# hub.net
KiCad netlist of a schematic drawn in EAGLE
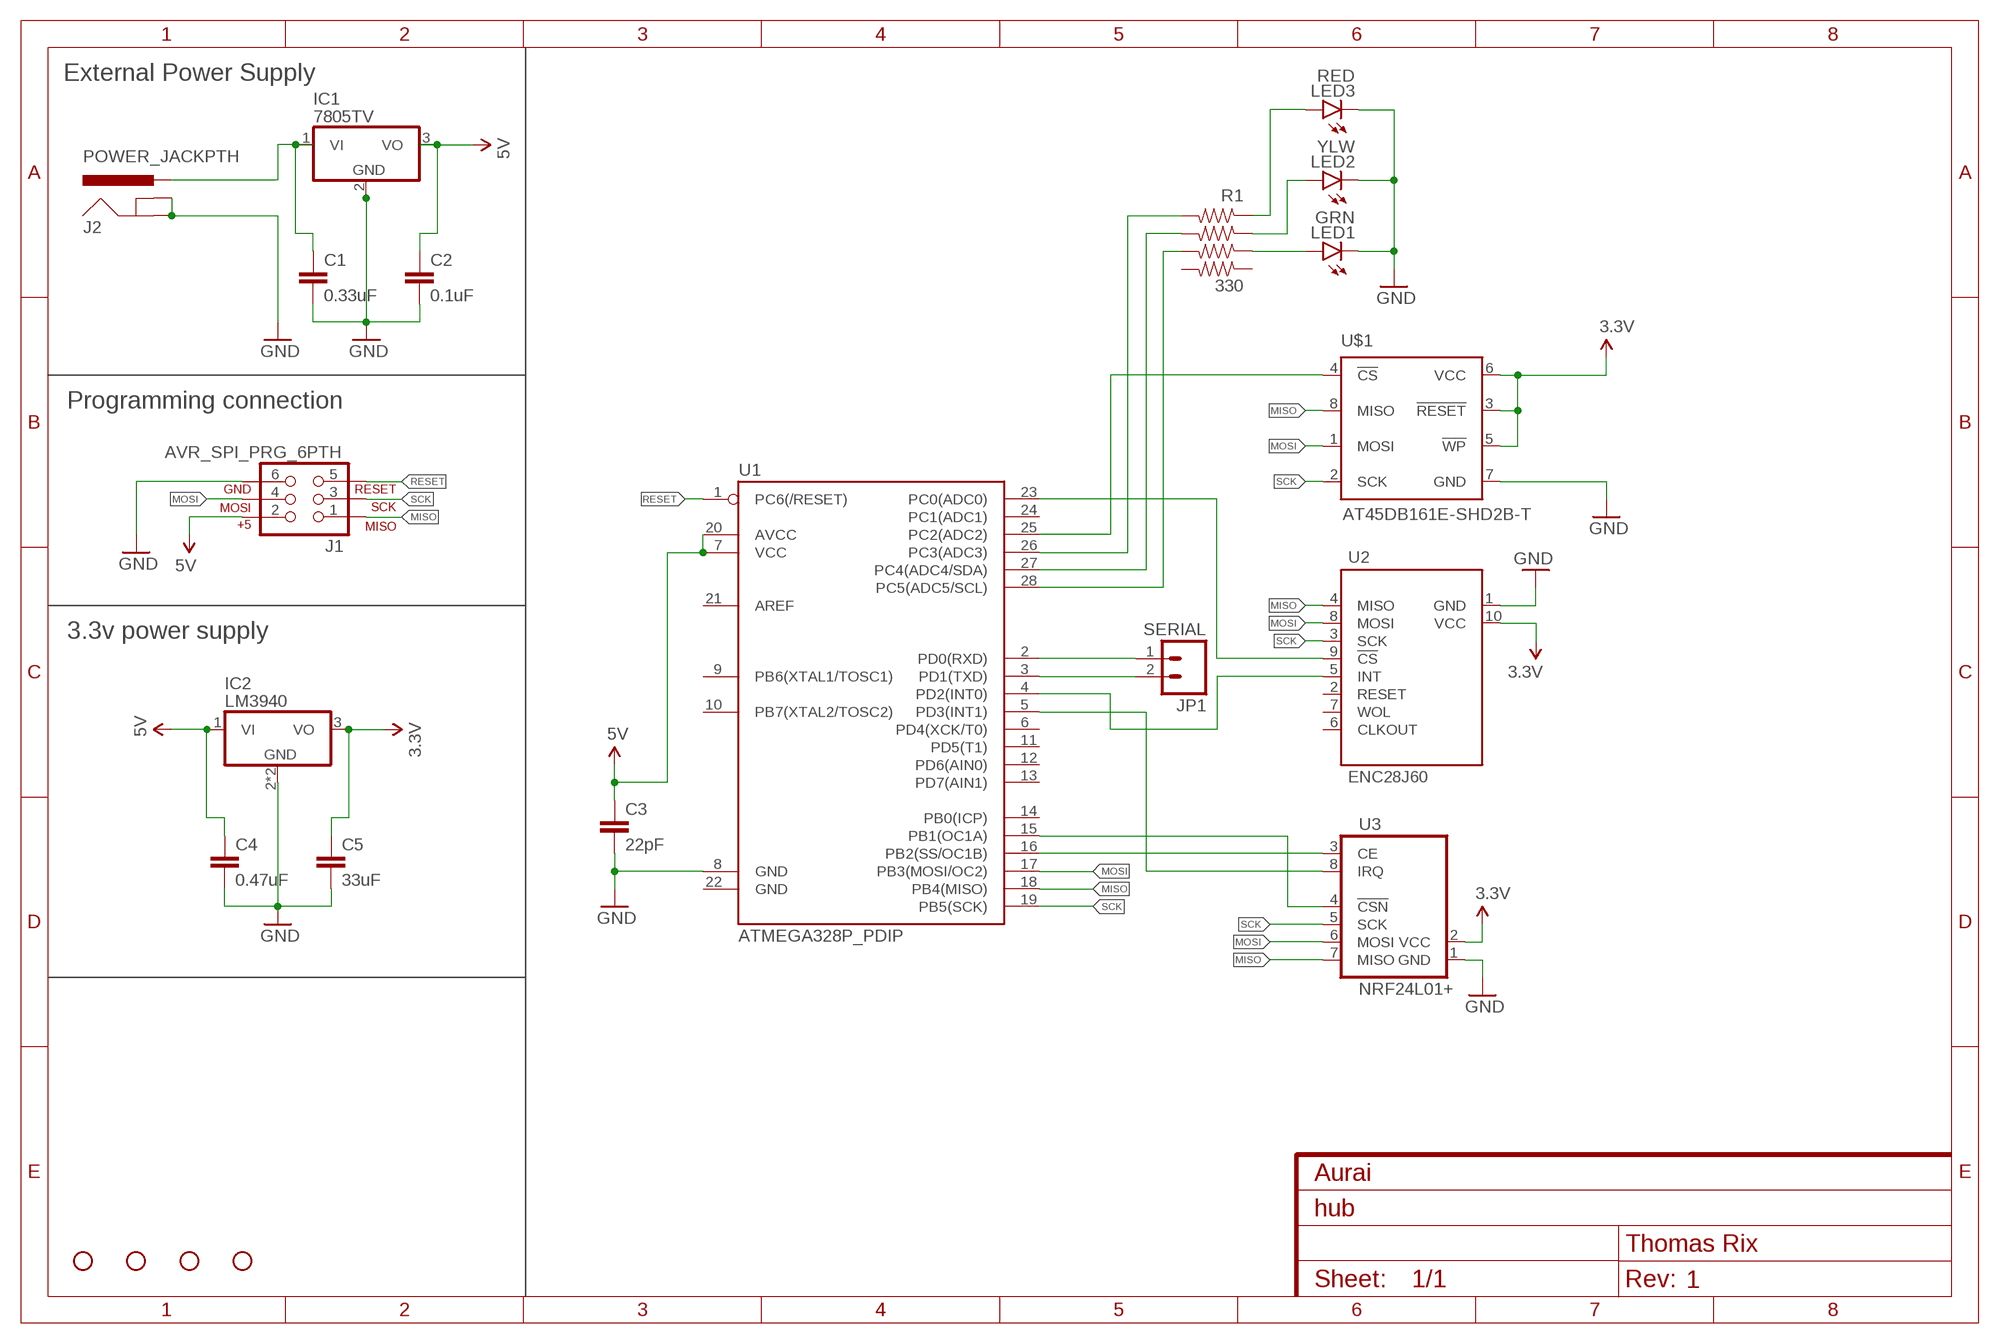
[diagram p0: schematic, sheet 1]

(export (version "E")
  (design (tool "Eeschema 10.0.6"))
  (components
    (comp (ref "C1")
      (value "0.33uF")
      (footprint "eagle-import:0805")
      (libsource (lib "eagle-import") (part "CAP0805"))
    )
    (comp (ref "C2")
      (value "0.1uF")
      (footprint "eagle-import:0805")
      (libsource (lib "eagle-import") (part "CAP0805"))
    )
    (comp (ref "C3")
      (value "22pF")
      (footprint "eagle-import:0805")
      (libsource (lib "eagle-import") (part "SparkFun-Passives_CAP0805"))
    )
    (comp (ref "C4")
      (value "0.47uF")
      (footprint "eagle-import:0805")
      (libsource (lib "eagle-import") (part "CAP0805"))
    )
    (comp (ref "C5")
      (value "33uF")
      (footprint "eagle-import:0805")
      (libsource (lib "eagle-import") (part "CAP0805"))
    )
    (comp (ref "IC1")
      (value "7805TV")
      (footprint "eagle-import:TO220V")
      (libsource (lib "eagle-import") (part "78TV05"))
    )
    (comp (ref "IC2")
      (value "LM3940")
      (footprint "eagle-import:SOT223")
      (libsource (lib "eagle-import") (part "LM3940"))
    )
    (comp (ref "J1")
      (value "AVR_SPI_PRG_6PTH")
      (footprint "eagle-import:2X3")
      (libsource (lib "eagle-import") (part "AVR_SPI_PRG_6PTH"))
    )
    (comp (ref "J2")
      (value "POWER_JACKPTH")
      (footprint "eagle-import:POWER_JACK_PTH")
      (libsource (lib "eagle-import") (part "POWER_JACKPTH"))
    )
    (comp (ref "JP1")
      (value "SERIAL")
      (footprint "eagle-import:1X02")
      (libsource (lib "eagle-import") (part "M02PTH"))
    )
    (comp (ref "LED1")
      (value "GRN")
      (footprint "eagle-import:LED-1206")
      (libsource (lib "eagle-import") (part "LED1206"))
    )
    (comp (ref "LED2")
      (value "YLW")
      (footprint "eagle-import:LED-1206")
      (libsource (lib "eagle-import") (part "LED1206"))
    )
    (comp (ref "LED3")
      (value "RED")
      (footprint "eagle-import:LED-1206")
      (libsource (lib "eagle-import") (part "LED1206"))
    )
    (comp (ref "R1")
      (value "330")
      (footprint "eagle-import:CRA06S08")
      (libsource (lib "eagle-import") (part "CRA06ES08"))
    )
    (comp (ref "STANDOFF1")
      (value "STAND-OFF")
      (footprint "eagle-import:STAND-OFF")
      (libsource (lib "eagle-import") (part "STAND-OFF"))
    )
    (comp (ref "STANDOFF2")
      (value "STAND-OFF")
      (footprint "eagle-import:STAND-OFF")
      (libsource (lib "eagle-import") (part "STAND-OFF"))
    )
    (comp (ref "STANDOFF3")
      (value "STAND-OFF")
      (footprint "eagle-import:STAND-OFF")
      (libsource (lib "eagle-import") (part "STAND-OFF"))
    )
    (comp (ref "STANDOFF4")
      (value "STAND-OFF")
      (footprint "eagle-import:STAND-OFF")
      (libsource (lib "eagle-import") (part "STAND-OFF"))
    )
    (comp (ref "U$1")
      (value "AT45DB161E-SHD2B-T")
      (footprint "eagle-import:SO08-EIAJ")
      (libsource (lib "eagle-import") (part "AT45DB161E-SHD2B-T"))
    )
    (comp (ref "U1")
      (value "ATMEGA328P_PDIP")
      (footprint "eagle-import:DIL28-3")
      (libsource (lib "eagle-import") (part "ATMEGA328P_PDIP"))
    )
    (comp (ref "U2")
      (value "ENC28J60")
      (footprint "eagle-import:ENC28J60_HEADER")
      (libsource (lib "eagle-import") (part "ENC28J60"))
    )
    (comp (ref "U3")
      (value "NRF24L01+")
      (footprint "eagle-import:NRF24L01_HEADER")
      (libsource (lib "eagle-import") (part "NRF24L01+"))
    )
  )
  (nets
    (net (code "1") (name "3.3V") (class "Default")
      (node (ref "C5") (pin "1") (pinfunction "1_1") (pintype "passive"))
      (node (ref "IC2") (pin "3") (pinfunction "VO_3") (pintype "passive"))
      (node (ref "U$1") (pin "3") (pinfunction "~{RESET}_3") (pintype "input"))
      (node (ref "U$1") (pin "5") (pinfunction "~{WP}_5") (pintype "input"))
      (node (ref "U$1") (pin "6") (pinfunction "VCC_6") (pintype "power_in"))
      (node (ref "U2") (pin "10") (pinfunction "VCC_10") (pintype "power_in"))
      (node (ref "U3") (pin "2") (pinfunction "VCC_2") (pintype "power_in"))
    )
    (net (code "2") (name "5V") (class "Default")
      (node (ref "C2") (pin "1") (pinfunction "1_1") (pintype "passive"))
      (node (ref "C3") (pin "1") (pinfunction "1_1") (pintype "passive"))
      (node (ref "C4") (pin "1") (pinfunction "1_1") (pintype "passive"))
      (node (ref "IC1") (pin "3") (pinfunction "VO_3") (pintype "passive"))
      (node (ref "IC2") (pin "1") (pinfunction "VI_1") (pintype "input"))
      (node (ref "J1") (pin "2") (pinfunction "2_2") (pintype "passive"))
      (node (ref "U1") (pin "20") (pinfunction "AVCC_20") (pintype "bidirectional"))
      (node (ref "U1") (pin "7") (pinfunction "VCC_7") (pintype "bidirectional"))
    )
    (net (code "3") (name "GND") (class "Default")
      (node (ref "C1") (pin "2") (pinfunction "2_2") (pintype "passive"))
      (node (ref "C2") (pin "2") (pinfunction "2_2") (pintype "passive"))
      (node (ref "C3") (pin "2") (pinfunction "2_2") (pintype "passive"))
      (node (ref "C4") (pin "2") (pinfunction "2_2") (pintype "passive"))
      (node (ref "C5") (pin "2") (pinfunction "2_2") (pintype "passive"))
      (node (ref "IC1") (pin "2") (pinfunction "GND_2") (pintype "passive"))
      (node (ref "IC2") (pin "2") (pinfunction "GND_2") (pintype "power_in"))
      (node (ref "IC2") (pin "4") (pinfunction "GND_4") (pintype "power_in"))
      (node (ref "J1") (pin "6") (pinfunction "6_6") (pintype "passive"))
      (node (ref "J2") (pin "GND") (pinfunction "GND_GND") (pintype "bidirectional"))
      (node (ref "J2") (pin "GNDBREAK") (pinfunction "GNDBREAK_GNDBREAK") (pintype "bidirectional"))
      (node (ref "LED1") (pin "C") (pinfunction "C_C") (pintype "passive"))
      (node (ref "LED2") (pin "C") (pinfunction "C_C") (pintype "passive"))
      (node (ref "LED3") (pin "C") (pinfunction "C_C") (pintype "passive"))
      (node (ref "U$1") (pin "7") (pinfunction "GND_7") (pintype "power_in"))
      (node (ref "U1") (pin "8") (pinfunction "GND_8") (pintype "bidirectional"))
      (node (ref "U2") (pin "1") (pinfunction "GND_1") (pintype "power_in"))
      (node (ref "U3") (pin "1") (pinfunction "GND_1") (pintype "power_in"))
    )
    (net (code "4") (name "MISO") (class "Default")
      (node (ref "J1") (pin "1") (pinfunction "1_1") (pintype "passive"))
      (node (ref "U$1") (pin "8") (pinfunction "MISO_8") (pintype "output"))
      (node (ref "U1") (pin "18") (pinfunction "PB4(MISO)_18") (pintype "bidirectional"))
      (node (ref "U2") (pin "4") (pinfunction "MISO_4") (pintype "output"))
      (node (ref "U3") (pin "7") (pinfunction "MISO_7") (pintype "output"))
    )
    (net (code "5") (name "MOSI") (class "Default")
      (node (ref "J1") (pin "4") (pinfunction "4_4") (pintype "passive"))
      (node (ref "U$1") (pin "1") (pinfunction "MOSI_1") (pintype "input"))
      (node (ref "U1") (pin "17") (pinfunction "PB3(MOSI/OC2)_17") (pintype "bidirectional"))
      (node (ref "U2") (pin "8") (pinfunction "MOSI_8") (pintype "input"))
      (node (ref "U3") (pin "6") (pinfunction "MOSI_6") (pintype "input"))
    )
    (net (code "6") (name "Net-(IC1-VI)") (class "Default")
      (node (ref "C1") (pin "1") (pinfunction "1_1") (pintype "passive"))
      (node (ref "IC1") (pin "1") (pinfunction "VI_1") (pintype "input"))
      (node (ref "J2") (pin "PWR") (pinfunction "PWR_PWR") (pintype "bidirectional"))
    )
    (net (code "7") (name "Net-(R1-R1A)") (class "Default")
      (node (ref "LED3") (pin "A") (pinfunction "A_A") (pintype "passive"))
      (node (ref "R1") (pin "1") (pinfunction "R1A_1") (pintype "passive"))
    )
    (net (code "8") (name "Net-(R1-R1B)") (class "Default")
      (node (ref "R1") (pin "8") (pinfunction "R1B_8") (pintype "passive"))
      (node (ref "U1") (pin "26") (pinfunction "PC3(ADC3)_26") (pintype "bidirectional"))
    )
    (net (code "9") (name "Net-(R1-R2A)") (class "Default")
      (node (ref "LED2") (pin "A") (pinfunction "A_A") (pintype "passive"))
      (node (ref "R1") (pin "2") (pinfunction "R2A_2") (pintype "passive"))
    )
    (net (code "10") (name "Net-(R1-R2B)") (class "Default")
      (node (ref "R1") (pin "7") (pinfunction "R2B_7") (pintype "passive"))
      (node (ref "U1") (pin "27") (pinfunction "PC4(ADC4/SDA)_27") (pintype "bidirectional"))
    )
    (net (code "11") (name "Net-(R1-R3A)") (class "Default")
      (node (ref "LED1") (pin "A") (pinfunction "A_A") (pintype "passive"))
      (node (ref "R1") (pin "3") (pinfunction "R3A_3") (pintype "passive"))
    )
    (net (code "12") (name "Net-(R1-R3B)") (class "Default")
      (node (ref "R1") (pin "6") (pinfunction "R3B_6") (pintype "passive"))
      (node (ref "U1") (pin "28") (pinfunction "PC5(ADC5/SCL)_28") (pintype "bidirectional"))
    )
    (net (code "13") (name "Net-(U$1-~{CS})") (class "Default")
      (node (ref "U$1") (pin "4") (pinfunction "~{CS}_4") (pintype "input"))
      (node (ref "U1") (pin "25") (pinfunction "PC2(ADC2)_25") (pintype "bidirectional"))
    )
    (net (code "14") (name "Net-(U1-PB1(OC1A))") (class "Default")
      (node (ref "U1") (pin "15") (pinfunction "PB1(OC1A)_15") (pintype "bidirectional"))
      (node (ref "U3") (pin "4") (pinfunction "~{CSN}_4") (pintype "input"))
    )
    (net (code "15") (name "Net-(U1-PB2(SS{slash}OC1B))") (class "Default")
      (node (ref "U1") (pin "16") (pinfunction "PB2(SS/OC1B)_16") (pintype "bidirectional"))
      (node (ref "U3") (pin "3") (pinfunction "CE_3") (pintype "input"))
    )
    (net (code "16") (name "Net-(U1-PC0(ADC0))") (class "Default")
      (node (ref "U1") (pin "23") (pinfunction "PC0(ADC0)_23") (pintype "bidirectional"))
      (node (ref "U2") (pin "9") (pinfunction "~{CS}_9") (pintype "input"))
    )
    (net (code "17") (name "Net-(U1-PD0(RXD))") (class "Default")
      (node (ref "JP1") (pin "1") (pinfunction "1_1") (pintype "passive"))
      (node (ref "U1") (pin "2") (pinfunction "PD0(RXD)_2") (pintype "bidirectional"))
    )
    (net (code "18") (name "Net-(U1-PD1(TXD))") (class "Default")
      (node (ref "JP1") (pin "2") (pinfunction "2_2") (pintype "passive"))
      (node (ref "U1") (pin "3") (pinfunction "PD1(TXD)_3") (pintype "bidirectional"))
    )
    (net (code "19") (name "Net-(U1-PD2(INT0))") (class "Default")
      (node (ref "U1") (pin "4") (pinfunction "PD2(INT0)_4") (pintype "bidirectional"))
      (node (ref "U2") (pin "5") (pinfunction "INT_5") (pintype "output"))
    )
    (net (code "20") (name "Net-(U1-PD3(INT1))") (class "Default")
      (node (ref "U1") (pin "5") (pinfunction "PD3(INT1)_5") (pintype "bidirectional"))
      (node (ref "U3") (pin "8") (pinfunction "IRQ_8") (pintype "output"))
    )
    (net (code "21") (name "RESET") (class "Default")
      (node (ref "J1") (pin "5") (pinfunction "5_5") (pintype "passive"))
      (node (ref "U1") (pin "1") (pinfunction "PC6(/RESET)_1") (pintype "bidirectional"))
    )
    (net (code "22") (name "SCK") (class "Default")
      (node (ref "J1") (pin "3") (pinfunction "3_3") (pintype "passive"))
      (node (ref "U$1") (pin "2") (pinfunction "SCK_2") (pintype "input"))
      (node (ref "U1") (pin "19") (pinfunction "PB5(SCK)_19") (pintype "bidirectional"))
      (node (ref "U2") (pin "3") (pinfunction "SCK_3") (pintype "input"))
      (node (ref "U3") (pin "5") (pinfunction "SCK_5") (pintype "output"))
    )
    (net (code "23") (name "unconnected-(R1-R4A-Pad4)") (class "Default")
      (node (ref "R1") (pin "4") (pinfunction "R4A_4") (pintype "passive"))
    )
    (net (code "24") (name "unconnected-(R1-R4B-Pad5)") (class "Default")
      (node (ref "R1") (pin "5") (pinfunction "R4B_5") (pintype "passive"))
    )
    (net (code "25") (name "unconnected-(U1-AREF-Pad21)") (class "Default")
      (node (ref "U1") (pin "21") (pinfunction "AREF_21") (pintype "bidirectional"))
    )
    (net (code "26") (name "unconnected-(U1-GND-Pad22)") (class "Default")
      (node (ref "U1") (pin "22") (pinfunction "GND_22") (pintype "bidirectional"))
    )
    (net (code "27") (name "unconnected-(U1-PB0(ICP)-Pad14)") (class "Default")
      (node (ref "U1") (pin "14") (pinfunction "PB0(ICP)_14") (pintype "bidirectional"))
    )
    (net (code "28") (name "unconnected-(U1-PB6(XTAL1{slash}TOSC1)-Pad9)") (class "Default")
      (node (ref "U1") (pin "9") (pinfunction "PB6(XTAL1/TOSC1)_9") (pintype "bidirectional"))
    )
    (net (code "29") (name "unconnected-(U1-PB7(XTAL2{slash}TOSC2)-Pad10)") (class "Default")
      (node (ref "U1") (pin "10") (pinfunction "PB7(XTAL2/TOSC2)_10") (pintype "bidirectional"))
    )
    (net (code "30") (name "unconnected-(U1-PC1(ADC1)-Pad24)") (class "Default")
      (node (ref "U1") (pin "24") (pinfunction "PC1(ADC1)_24") (pintype "bidirectional"))
    )
    (net (code "31") (name "unconnected-(U1-PD4(XCK{slash}T0)-Pad6)") (class "Default")
      (node (ref "U1") (pin "6") (pinfunction "PD4(XCK/T0)_6") (pintype "bidirectional"))
    )
    (net (code "32") (name "unconnected-(U1-PD5(T1)-Pad11)") (class "Default")
      (node (ref "U1") (pin "11") (pinfunction "PD5(T1)_11") (pintype "bidirectional"))
    )
    (net (code "33") (name "unconnected-(U1-PD6(AIN0)-Pad12)") (class "Default")
      (node (ref "U1") (pin "12") (pinfunction "PD6(AIN0)_12") (pintype "bidirectional"))
    )
    (net (code "34") (name "unconnected-(U1-PD7(AIN1)-Pad13)") (class "Default")
      (node (ref "U1") (pin "13") (pinfunction "PD7(AIN1)_13") (pintype "bidirectional"))
    )
    (net (code "35") (name "unconnected-(U2-CLKOUT-Pad6)") (class "Default")
      (node (ref "U2") (pin "6") (pinfunction "CLKOUT_6") (pintype "output"))
    )
    (net (code "36") (name "unconnected-(U2-RESET-Pad2)") (class "Default")
      (node (ref "U2") (pin "2") (pinfunction "RESET_2") (pintype "bidirectional"))
    )
    (net (code "37") (name "unconnected-(U2-WOL-Pad7)") (class "Default")
      (node (ref "U2") (pin "7") (pinfunction "WOL_7") (pintype "bidirectional"))
    )
  )
)
